# Power_Supply.net
KiCad netlist of a schematic drawn in Altium Designer
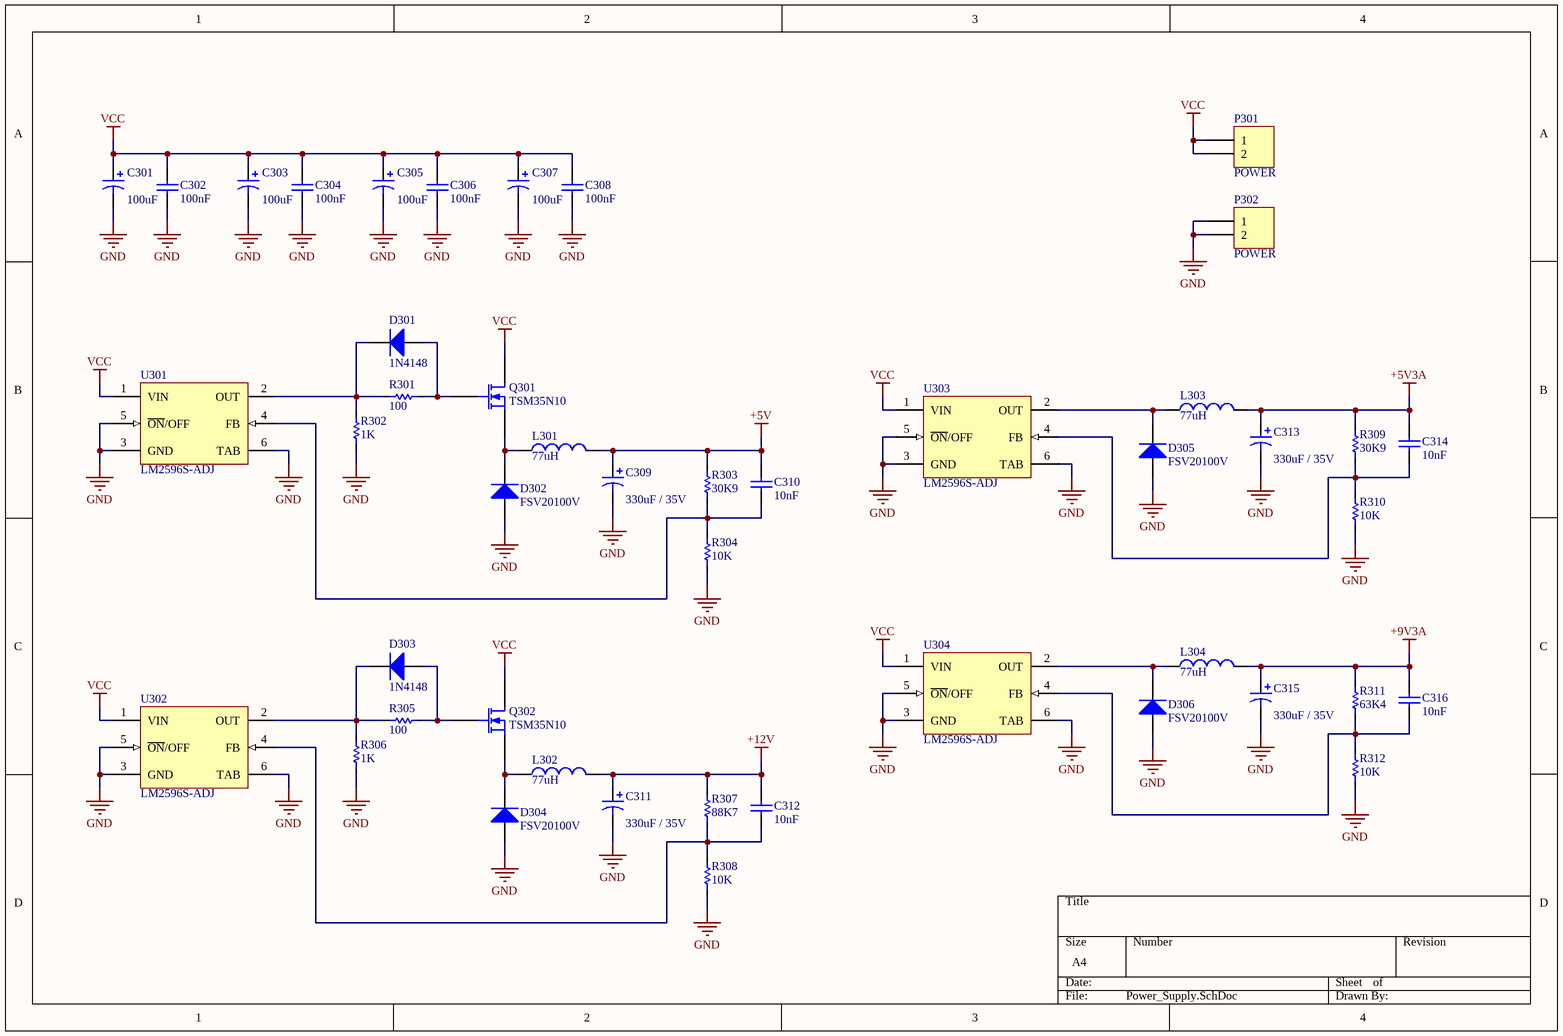
[diagram p0: Power_Supply.SchDoc]

(export (version "E")
  (design (tool "Eeschema 10.0.6"))
  (components
    (comp (ref "C301")
      (value "100uF")
      (footprint "F55")
      (description "Polarized Capacitor (Surface Mount)")
      (fields (field (name "Comment") "Cap Pol3") (field (name "PUBLISHER") "Altium Limited"))
      (libsource (lib "Miscellaneous Devices") (part "Cap Pol3"))
    )
    (comp (ref "C302")
      (value "Cap Ceramico SMD")
      (footprint "C0603")
      (description "Cap Ceramico SMD 0805")
      (fields (field (name "VALOR") "100nF"))
      (libsource (lib "RUF-Dispositivos-Grales") (part "Cap Ceramico SMD"))
    )
    (comp (ref "C303")
      (value "100uF")
      (footprint "F55")
      (description "Polarized Capacitor (Surface Mount)")
      (fields (field (name "Comment") "Cap Pol3") (field (name "PUBLISHER") "Altium Limited"))
      (libsource (lib "Miscellaneous Devices") (part "Cap Pol3"))
    )
    (comp (ref "C304")
      (value "Cap Ceramico SMD")
      (footprint "C0603")
      (description "Cap Ceramico SMD 0805")
      (fields (field (name "VALOR") "100nF"))
      (libsource (lib "RUF-Dispositivos-Grales") (part "Cap Ceramico SMD"))
    )
    (comp (ref "C305")
      (value "100uF")
      (footprint "F55")
      (description "Polarized Capacitor (Surface Mount)")
      (fields (field (name "Comment") "Cap Pol3") (field (name "PUBLISHER") "Altium Limited"))
      (libsource (lib "Miscellaneous Devices") (part "Cap Pol3"))
    )
    (comp (ref "C306")
      (value "Cap Ceramico SMD")
      (footprint "C0603")
      (description "Cap Ceramico SMD 0805")
      (fields (field (name "VALOR") "100nF"))
      (libsource (lib "RUF-Dispositivos-Grales") (part "Cap Ceramico SMD"))
    )
    (comp (ref "C307")
      (value "100uF")
      (footprint "F55")
      (description "Polarized Capacitor (Surface Mount)")
      (fields (field (name "Comment") "Cap Pol3") (field (name "PUBLISHER") "Altium Limited"))
      (libsource (lib "Miscellaneous Devices") (part "Cap Pol3"))
    )
    (comp (ref "C308")
      (value "Cap Ceramico SMD")
      (footprint "C0603")
      (description "Cap Ceramico SMD 0805")
      (fields (field (name "VALOR") "100nF"))
      (libsource (lib "RUF-Dispositivos-Grales") (part "Cap Ceramico SMD"))
    )
    (comp (ref "C309")
      (value "330uF / 35V")
      (footprint "MCL1GS")
      (description "Polarized Capacitor (Surface Mount)")
      (fields (field (name "Comment") "Cap Pol3") (field (name "PUBLISHER") "Altium Limited"))
      (libsource (lib "Miscellaneous Devices") (part "Cap Pol3"))
    )
    (comp (ref "C310")
      (value "Cap Ceramico SMD")
      (footprint "C0603")
      (description "Cap Ceramico SMD 0805")
      (fields (field (name "VALOR") "10nF"))
      (libsource (lib "RUF-Dispositivos-Grales") (part "Cap Ceramico SMD"))
    )
    (comp (ref "C311")
      (value "330uF / 35V")
      (footprint "MCL1GS")
      (description "Polarized Capacitor (Surface Mount)")
      (fields (field (name "Comment") "Cap Pol3") (field (name "PUBLISHER") "Altium Limited"))
      (libsource (lib "Miscellaneous Devices") (part "Cap Pol3"))
    )
    (comp (ref "C312")
      (value "Cap Ceramico SMD")
      (footprint "C0603")
      (description "Cap Ceramico SMD 0805")
      (fields (field (name "VALOR") "10nF"))
      (libsource (lib "RUF-Dispositivos-Grales") (part "Cap Ceramico SMD"))
    )
    (comp (ref "C313")
      (value "330uF / 35V")
      (footprint "MCL1GS")
      (description "Polarized Capacitor (Surface Mount)")
      (fields (field (name "Comment") "Cap Pol3") (field (name "PUBLISHER") "Altium Limited"))
      (libsource (lib "Miscellaneous Devices") (part "Cap Pol3"))
    )
    (comp (ref "C314")
      (value "Cap Ceramico SMD")
      (footprint "C0603")
      (description "Cap Ceramico SMD 0805")
      (fields (field (name "VALOR") "10nF"))
      (libsource (lib "RUF-Dispositivos-Grales") (part "Cap Ceramico SMD"))
    )
    (comp (ref "C315")
      (value "330uF / 35V")
      (footprint "MCL1GS")
      (description "Polarized Capacitor (Surface Mount)")
      (fields (field (name "Comment") "Cap Pol3") (field (name "PUBLISHER") "Altium Limited"))
      (libsource (lib "Miscellaneous Devices") (part "Cap Pol3"))
    )
    (comp (ref "C316")
      (value "Cap Ceramico SMD")
      (footprint "C0603")
      (description "Cap Ceramico SMD 0805")
      (fields (field (name "VALOR") "10nF"))
      (libsource (lib "RUF-Dispositivos-Grales") (part "Cap Ceramico SMD"))
    )
    (comp (ref "D301")
      (value "Diodo Rectificador SMD")
      (footprint "SOD-80")
      (description "Diodo Rectificador")
      (fields (field (name "VALOR") "1N4148"))
      (libsource (lib "RUF-Dispositivos-Grales") (part "Diodo Rectificador SMD"))
    )
    (comp (ref "D302")
      (value "Diodo Rectificador SMD")
      (footprint "TO-277-3")
      (description "Diodo Rectificador")
      (fields (field (name "VALOR") "FSV20100V"))
      (libsource (lib "RUF-Dispositivos-Grales") (part "Diodo Rectificador SMD"))
    )
    (comp (ref "D303")
      (value "Diodo Rectificador SMD")
      (footprint "SOD-80")
      (description "Diodo Rectificador")
      (fields (field (name "VALOR") "1N4148"))
      (libsource (lib "RUF-Dispositivos-Grales") (part "Diodo Rectificador SMD"))
    )
    (comp (ref "D304")
      (value "Diodo Rectificador SMD")
      (footprint "TO-277-3")
      (description "Diodo Rectificador")
      (fields (field (name "VALOR") "FSV20100V"))
      (libsource (lib "RUF-Dispositivos-Grales") (part "Diodo Rectificador SMD"))
    )
    (comp (ref "D305")
      (value "Diodo Rectificador SMD")
      (footprint "TO-277-3")
      (description "Diodo Rectificador")
      (fields (field (name "VALOR") "FSV20100V"))
      (libsource (lib "RUF-Dispositivos-Grales") (part "Diodo Rectificador SMD"))
    )
    (comp (ref "D306")
      (value "Diodo Rectificador SMD")
      (footprint "TO-277-3")
      (description "Diodo Rectificador")
      (fields (field (name "VALOR") "FSV20100V"))
      (libsource (lib "RUF-Dispositivos-Grales") (part "Diodo Rectificador SMD"))
    )
    (comp (ref "L301")
      (value "77uH")
      (footprint "KM-3.0")
      (description "Inductor")
      (fields (field (name "PUBLISHER") "Altium Limited"))
      (libsource (lib "Miscellaneous Devices") (part "Inductor"))
    )
    (comp (ref "L302")
      (value "77uH")
      (footprint "KM-3.0")
      (description "Inductor")
      (fields (field (name "PUBLISHER") "Altium Limited"))
      (libsource (lib "Miscellaneous Devices") (part "Inductor"))
    )
    (comp (ref "L303")
      (value "77uH")
      (footprint "KM-3.0")
      (description "Inductor")
      (fields (field (name "PUBLISHER") "Altium Limited"))
      (libsource (lib "Miscellaneous Devices") (part "Inductor"))
    )
    (comp (ref "L304")
      (value "77uH")
      (footprint "KM-3.0")
      (description "Inductor")
      (fields (field (name "PUBLISHER") "Altium Limited"))
      (libsource (lib "Miscellaneous Devices") (part "Inductor"))
    )
    (comp (ref "P301")
      (value "POWER")
      (footprint "Terminal_2way_508")
      (description "Header, 2-Pin")
      (fields (field (name "PUBLISHER") "Altium Limited"))
      (libsource (lib "Miscellaneous Connectors") (part "Header 2"))
    )
    (comp (ref "P302")
      (value "POWER")
      (footprint "Terminal_2way_508")
      (description "Header, 2-Pin")
      (fields (field (name "PUBLISHER") "Altium Limited"))
      (libsource (lib "Miscellaneous Connectors") (part "Header 2"))
    )
    (comp (ref "Q301")
      (value "TSM35N10")
      (footprint "TO-252AA_A_M")
      (description "N-Channel MOSFET")
      (fields (field (name "PUBLISHER") "Altium Limited"))
      (libsource (lib "Miscellaneous Devices") (part "MOSFET-N"))
    )
    (comp (ref "Q302")
      (value "TSM35N10")
      (footprint "TO-252AA_A_M")
      (description "N-Channel MOSFET")
      (fields (field (name "PUBLISHER") "Altium Limited"))
      (libsource (lib "Miscellaneous Devices") (part "MOSFET-N"))
    )
    (comp (ref "R301")
      (value "Res SMD")
      (footprint "R0603")
      (description "Res Smd")
      (fields (field (name "VALOR") "100"))
      (libsource (lib "RUF-Dispositivos-Grales") (part "Res SMD"))
    )
    (comp (ref "R302")
      (value "Res SMD")
      (footprint "R0603")
      (description "Res Smd")
      (fields (field (name "VALOR") "1K"))
      (libsource (lib "RUF-Dispositivos-Grales") (part "Res SMD"))
    )
    (comp (ref "R303")
      (value "Res SMD")
      (footprint "R0603")
      (description "Res Smd")
      (fields (field (name "VALOR") "30K9"))
      (libsource (lib "RUF-Dispositivos-Grales") (part "Res SMD"))
    )
    (comp (ref "R304")
      (value "Res SMD")
      (footprint "R0603")
      (description "Res Smd")
      (fields (field (name "VALOR") "10K"))
      (libsource (lib "RUF-Dispositivos-Grales") (part "Res SMD"))
    )
    (comp (ref "R305")
      (value "Res SMD")
      (footprint "R0603")
      (description "Res Smd")
      (fields (field (name "VALOR") "100"))
      (libsource (lib "RUF-Dispositivos-Grales") (part "Res SMD"))
    )
    (comp (ref "R306")
      (value "Res SMD")
      (footprint "R0603")
      (description "Res Smd")
      (fields (field (name "VALOR") "1K"))
      (libsource (lib "RUF-Dispositivos-Grales") (part "Res SMD"))
    )
    (comp (ref "R307")
      (value "Res SMD")
      (footprint "R0603")
      (description "Res Smd")
      (fields (field (name "VALOR") "88K7"))
      (libsource (lib "RUF-Dispositivos-Grales") (part "Res SMD"))
    )
    (comp (ref "R308")
      (value "Res SMD")
      (footprint "R0603")
      (description "Res Smd")
      (fields (field (name "VALOR") "10K"))
      (libsource (lib "RUF-Dispositivos-Grales") (part "Res SMD"))
    )
    (comp (ref "R309")
      (value "Res SMD")
      (footprint "R0603")
      (description "Res Smd")
      (fields (field (name "VALOR") "30K9"))
      (libsource (lib "RUF-Dispositivos-Grales") (part "Res SMD"))
    )
    (comp (ref "R310")
      (value "Res SMD")
      (footprint "R0603")
      (description "Res Smd")
      (fields (field (name "VALOR") "10K"))
      (libsource (lib "RUF-Dispositivos-Grales") (part "Res SMD"))
    )
    (comp (ref "R311")
      (value "Res SMD")
      (footprint "R0603")
      (description "Res Smd")
      (fields (field (name "VALOR") "63K4"))
      (libsource (lib "RUF-Dispositivos-Grales") (part "Res SMD"))
    )
    (comp (ref "R312")
      (value "Res SMD")
      (footprint "R0603")
      (description "Res Smd")
      (fields (field (name "VALOR") "10K"))
      (libsource (lib "RUF-Dispositivos-Grales") (part "Res SMD"))
    )
    (comp (ref "U301")
      (value "LM2596S-ADJ")
      (footprint "TS5B_M")
      (description "SIMPLE SWITCHER® Power Converter 150 KHz 3A Step-Down Voltage Regulator, 5-pin TO-263")
      (fields
        (field (name "MANUFACTURER") "National Semiconductor")
        (field (name "PUBLISHER") "Altium Limited")
      )
      (libsource (lib "NSC Switcher") (part "LM2596S-ADJ"))
    )
    (comp (ref "U302")
      (value "LM2596S-ADJ")
      (footprint "TS5B_M")
      (description "SIMPLE SWITCHER® Power Converter 150 KHz 3A Step-Down Voltage Regulator, 5-pin TO-263")
      (fields
        (field (name "MANUFACTURER") "National Semiconductor")
        (field (name "PUBLISHER") "Altium Limited")
      )
      (libsource (lib "NSC Switcher") (part "LM2596S-ADJ"))
    )
    (comp (ref "U303")
      (value "LM2596S-ADJ")
      (footprint "TS5B_M")
      (description "SIMPLE SWITCHER® Power Converter 150 KHz 3A Step-Down Voltage Regulator, 5-pin TO-263")
      (fields
        (field (name "MANUFACTURER") "National Semiconductor")
        (field (name "PUBLISHER") "Altium Limited")
      )
      (libsource (lib "NSC Switcher") (part "LM2596S-ADJ"))
    )
    (comp (ref "U304")
      (value "LM2596S-ADJ")
      (footprint "TS5B_M")
      (description "SIMPLE SWITCHER® Power Converter 150 KHz 3A Step-Down Voltage Regulator, 5-pin TO-263")
      (fields
        (field (name "MANUFACTURER") "National Semiconductor")
        (field (name "PUBLISHER") "Altium Limited")
      )
      (libsource (lib "NSC Switcher") (part "LM2596S-ADJ"))
    )
  )
  (nets
    (net (code "1") (name "+5V") (class "Default")
      (node (ref "C309") (pin "1") (pinfunction "1_1") (pintype "passive"))
      (node (ref "C310") (pin "1") (pinfunction "1_1") (pintype "passive"))
      (node (ref "L301") (pin "2") (pinfunction "2_2") (pintype "passive"))
      (node (ref "R303") (pin "1") (pinfunction "1_1") (pintype "passive"))
    )
    (net (code "2") (name "+5V3A") (class "Default")
      (node (ref "C313") (pin "1") (pinfunction "1_1") (pintype "passive"))
      (node (ref "C314") (pin "1") (pinfunction "1_1") (pintype "passive"))
      (node (ref "L303") (pin "2") (pinfunction "2_2") (pintype "passive"))
      (node (ref "R309") (pin "1") (pinfunction "1_1") (pintype "passive"))
    )
    (net (code "3") (name "+9V3A") (class "Default")
      (node (ref "C315") (pin "1") (pinfunction "1_1") (pintype "passive"))
      (node (ref "C316") (pin "1") (pinfunction "1_1") (pintype "passive"))
      (node (ref "L304") (pin "2") (pinfunction "2_2") (pintype "passive"))
      (node (ref "R311") (pin "1") (pinfunction "1_1") (pintype "passive"))
    )
    (net (code "4") (name "+12V") (class "Default")
      (node (ref "C311") (pin "1") (pinfunction "1_1") (pintype "passive"))
      (node (ref "C312") (pin "1") (pinfunction "1_1") (pintype "passive"))
      (node (ref "L302") (pin "2") (pinfunction "2_2") (pintype "passive"))
      (node (ref "R307") (pin "1") (pinfunction "1_1") (pintype "passive"))
    )
    (net (code "5") (name "GND") (class "Default")
      (node (ref "C301") (pin "2") (pinfunction "2_2") (pintype "passive"))
      (node (ref "C302") (pin "2") (pinfunction "2_2") (pintype "passive"))
      (node (ref "C303") (pin "2") (pinfunction "2_2") (pintype "passive"))
      (node (ref "C304") (pin "2") (pinfunction "2_2") (pintype "passive"))
      (node (ref "C305") (pin "2") (pinfunction "2_2") (pintype "passive"))
      (node (ref "C306") (pin "2") (pinfunction "2_2") (pintype "passive"))
      (node (ref "C307") (pin "2") (pinfunction "2_2") (pintype "passive"))
      (node (ref "C308") (pin "2") (pinfunction "2_2") (pintype "passive"))
      (node (ref "C309") (pin "2") (pinfunction "2_2") (pintype "passive"))
      (node (ref "C311") (pin "2") (pinfunction "2_2") (pintype "passive"))
      (node (ref "C313") (pin "2") (pinfunction "2_2") (pintype "passive"))
      (node (ref "C315") (pin "2") (pinfunction "2_2") (pintype "passive"))
      (node (ref "D302") (pin "1") (pinfunction "A_1") (pintype "passive"))
      (node (ref "D304") (pin "1") (pinfunction "A_1") (pintype "passive"))
      (node (ref "D305") (pin "1") (pinfunction "A_1") (pintype "passive"))
      (node (ref "D306") (pin "1") (pinfunction "A_1") (pintype "passive"))
      (node (ref "P302") (pin "1") (pinfunction "1_1") (pintype "passive"))
      (node (ref "P302") (pin "2") (pinfunction "2_2") (pintype "passive"))
      (node (ref "R302") (pin "2") (pinfunction "2_2") (pintype "passive"))
      (node (ref "R304") (pin "2") (pinfunction "2_2") (pintype "passive"))
      (node (ref "R306") (pin "2") (pinfunction "2_2") (pintype "passive"))
      (node (ref "R308") (pin "2") (pinfunction "2_2") (pintype "passive"))
      (node (ref "R310") (pin "2") (pinfunction "2_2") (pintype "passive"))
      (node (ref "R312") (pin "2") (pinfunction "2_2") (pintype "passive"))
      (node (ref "U301") (pin "3") (pinfunction "GND_3") (pintype "power_in"))
      (node (ref "U301") (pin "5") (pinfunction "~{ON}/OFF_5") (pintype "input"))
      (node (ref "U301") (pin "6") (pinfunction "TAB_6") (pintype "power_in"))
      (node (ref "U302") (pin "3") (pinfunction "GND_3") (pintype "power_in"))
      (node (ref "U302") (pin "5") (pinfunction "~{ON}/OFF_5") (pintype "input"))
      (node (ref "U302") (pin "6") (pinfunction "TAB_6") (pintype "power_in"))
      (node (ref "U303") (pin "3") (pinfunction "GND_3") (pintype "power_in"))
      (node (ref "U303") (pin "5") (pinfunction "~{ON}/OFF_5") (pintype "input"))
      (node (ref "U303") (pin "6") (pinfunction "TAB_6") (pintype "power_in"))
      (node (ref "U304") (pin "3") (pinfunction "GND_3") (pintype "power_in"))
      (node (ref "U304") (pin "5") (pinfunction "~{ON}/OFF_5") (pintype "input"))
      (node (ref "U304") (pin "6") (pinfunction "TAB_6") (pintype "power_in"))
    )
    (net (code "6") (name "Net-(D301-A)") (class "Default")
      (node (ref "D301") (pin "1") (pinfunction "A_1") (pintype "passive"))
      (node (ref "Q301") (pin "1") (pinfunction "G_1") (pintype "passive"))
      (node (ref "R301") (pin "1") (pinfunction "1_1") (pintype "passive"))
    )
    (net (code "7") (name "Net-(D301-K)") (class "Default")
      (node (ref "D301") (pin "2") (pinfunction "K_2") (pintype "passive"))
      (node (ref "R301") (pin "2") (pinfunction "2_2") (pintype "passive"))
      (node (ref "R302") (pin "1") (pinfunction "1_1") (pintype "passive"))
      (node (ref "U301") (pin "2") (pinfunction "OUT_2") (pintype "power_in"))
    )
    (net (code "8") (name "Net-(D302-K)") (class "Default")
      (node (ref "D302") (pin "2") (pinfunction "K_2") (pintype "passive"))
      (node (ref "L301") (pin "1") (pinfunction "1_1") (pintype "passive"))
      (node (ref "Q301") (pin "3") (pinfunction "S_3") (pintype "passive"))
    )
    (net (code "9") (name "Net-(D303-A)") (class "Default")
      (node (ref "D303") (pin "1") (pinfunction "A_1") (pintype "passive"))
      (node (ref "Q302") (pin "1") (pinfunction "G_1") (pintype "passive"))
      (node (ref "R305") (pin "1") (pinfunction "1_1") (pintype "passive"))
    )
    (net (code "10") (name "Net-(D303-K)") (class "Default")
      (node (ref "D303") (pin "2") (pinfunction "K_2") (pintype "passive"))
      (node (ref "R305") (pin "2") (pinfunction "2_2") (pintype "passive"))
      (node (ref "R306") (pin "1") (pinfunction "1_1") (pintype "passive"))
      (node (ref "U302") (pin "2") (pinfunction "OUT_2") (pintype "power_in"))
    )
    (net (code "11") (name "Net-(D304-K)") (class "Default")
      (node (ref "D304") (pin "2") (pinfunction "K_2") (pintype "passive"))
      (node (ref "L302") (pin "1") (pinfunction "1_1") (pintype "passive"))
      (node (ref "Q302") (pin "3") (pinfunction "S_3") (pintype "passive"))
    )
    (net (code "12") (name "Net-(D305-K)") (class "Default")
      (node (ref "D305") (pin "2") (pinfunction "K_2") (pintype "passive"))
      (node (ref "L303") (pin "1") (pinfunction "1_1") (pintype "passive"))
      (node (ref "U303") (pin "2") (pinfunction "OUT_2") (pintype "power_in"))
    )
    (net (code "13") (name "Net-(D306-K)") (class "Default")
      (node (ref "D306") (pin "2") (pinfunction "K_2") (pintype "passive"))
      (node (ref "L304") (pin "1") (pinfunction "1_1") (pintype "passive"))
      (node (ref "U304") (pin "2") (pinfunction "OUT_2") (pintype "power_in"))
    )
    (net (code "14") (name "Net-(U301-FB)") (class "Default")
      (node (ref "C310") (pin "2") (pinfunction "2_2") (pintype "passive"))
      (node (ref "R303") (pin "2") (pinfunction "2_2") (pintype "passive"))
      (node (ref "R304") (pin "1") (pinfunction "1_1") (pintype "passive"))
      (node (ref "U301") (pin "4") (pinfunction "FB_4") (pintype "input"))
    )
    (net (code "15") (name "Net-(U302-FB)") (class "Default")
      (node (ref "C312") (pin "2") (pinfunction "2_2") (pintype "passive"))
      (node (ref "R307") (pin "2") (pinfunction "2_2") (pintype "passive"))
      (node (ref "R308") (pin "1") (pinfunction "1_1") (pintype "passive"))
      (node (ref "U302") (pin "4") (pinfunction "FB_4") (pintype "input"))
    )
    (net (code "16") (name "Net-(U303-FB)") (class "Default")
      (node (ref "C314") (pin "2") (pinfunction "2_2") (pintype "passive"))
      (node (ref "R309") (pin "2") (pinfunction "2_2") (pintype "passive"))
      (node (ref "R310") (pin "1") (pinfunction "1_1") (pintype "passive"))
      (node (ref "U303") (pin "4") (pinfunction "FB_4") (pintype "input"))
    )
    (net (code "17") (name "Net-(U304-FB)") (class "Default")
      (node (ref "C316") (pin "2") (pinfunction "2_2") (pintype "passive"))
      (node (ref "R311") (pin "2") (pinfunction "2_2") (pintype "passive"))
      (node (ref "R312") (pin "1") (pinfunction "1_1") (pintype "passive"))
      (node (ref "U304") (pin "4") (pinfunction "FB_4") (pintype "input"))
    )
    (net (code "18") (name "VCC") (class "Default")
      (node (ref "C301") (pin "1") (pinfunction "1_1") (pintype "passive"))
      (node (ref "C302") (pin "1") (pinfunction "1_1") (pintype "passive"))
      (node (ref "C303") (pin "1") (pinfunction "1_1") (pintype "passive"))
      (node (ref "C304") (pin "1") (pinfunction "1_1") (pintype "passive"))
      (node (ref "C305") (pin "1") (pinfunction "1_1") (pintype "passive"))
      (node (ref "C306") (pin "1") (pinfunction "1_1") (pintype "passive"))
      (node (ref "C307") (pin "1") (pinfunction "1_1") (pintype "passive"))
      (node (ref "C308") (pin "1") (pinfunction "1_1") (pintype "passive"))
      (node (ref "P301") (pin "1") (pinfunction "1_1") (pintype "passive"))
      (node (ref "P301") (pin "2") (pinfunction "2_2") (pintype "passive"))
      (node (ref "Q301") (pin "4") (pinfunction "D_4") (pintype "passive"))
      (node (ref "Q302") (pin "4") (pinfunction "D_4") (pintype "passive"))
      (node (ref "U301") (pin "1") (pinfunction "VIN_1") (pintype "power_in"))
      (node (ref "U302") (pin "1") (pinfunction "VIN_1") (pintype "power_in"))
      (node (ref "U303") (pin "1") (pinfunction "VIN_1") (pintype "power_in"))
      (node (ref "U304") (pin "1") (pinfunction "VIN_1") (pintype "power_in"))
    )
  )
)
